# Sheet1.net
KiCad netlist of a schematic drawn in Altium Designer
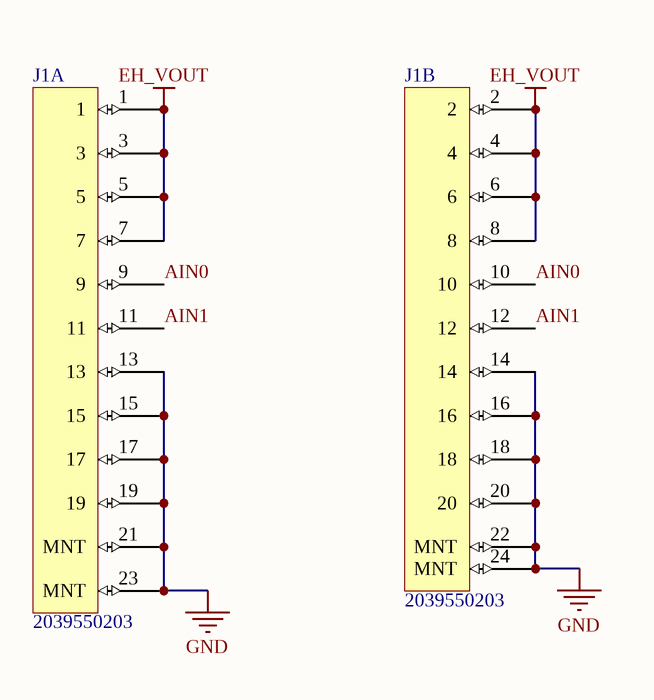
[diagram p0: Sheet1.SchDoc]

(export (version "E")
  (design (tool "Eeschema 10.0.6"))
  (components
    (comp (ref "J1")
      (value "2039550203")
      (footprint "2039550203")
      (libsource (lib "Molex_conn") (part "2039550203"))
    )
  )
  (nets
    (net (code "1") (name "/AIN0") (class "Default")
      (node (ref "J1") (pin "10") (pinfunction "10_10") (pintype "bidirectional"))
      (node (ref "J1") (pin "9") (pinfunction "9_9") (pintype "bidirectional"))
    )
    (net (code "2") (name "/AIN1") (class "Default")
      (node (ref "J1") (pin "11") (pinfunction "11_11") (pintype "bidirectional"))
      (node (ref "J1") (pin "12") (pinfunction "12_12") (pintype "bidirectional"))
    )
    (net (code "3") (name "EH_VOUT") (class "Default")
      (node (ref "J1") (pin "1") (pinfunction "1_1") (pintype "bidirectional"))
      (node (ref "J1") (pin "2") (pinfunction "2_2") (pintype "bidirectional"))
      (node (ref "J1") (pin "3") (pinfunction "3_3") (pintype "bidirectional"))
      (node (ref "J1") (pin "4") (pinfunction "4_4") (pintype "bidirectional"))
      (node (ref "J1") (pin "5") (pinfunction "5_5") (pintype "bidirectional"))
      (node (ref "J1") (pin "6") (pinfunction "6_6") (pintype "bidirectional"))
      (node (ref "J1") (pin "7") (pinfunction "7_7") (pintype "bidirectional"))
      (node (ref "J1") (pin "8") (pinfunction "8_8") (pintype "bidirectional"))
    )
    (net (code "4") (name "GND") (class "Default")
      (node (ref "J1") (pin "13") (pinfunction "13_13") (pintype "bidirectional"))
      (node (ref "J1") (pin "14") (pinfunction "14_14") (pintype "bidirectional"))
      (node (ref "J1") (pin "15") (pinfunction "15_15") (pintype "bidirectional"))
      (node (ref "J1") (pin "16") (pinfunction "16_16") (pintype "bidirectional"))
      (node (ref "J1") (pin "17") (pinfunction "17_17") (pintype "bidirectional"))
      (node (ref "J1") (pin "18") (pinfunction "18_18") (pintype "bidirectional"))
      (node (ref "J1") (pin "19") (pinfunction "19_19") (pintype "bidirectional"))
      (node (ref "J1") (pin "20") (pinfunction "20_20") (pintype "bidirectional"))
      (node (ref "J1") (pin "21") (pinfunction "MNT_21") (pintype "bidirectional"))
      (node (ref "J1") (pin "22") (pinfunction "MNT_22") (pintype "bidirectional"))
      (node (ref "J1") (pin "23") (pinfunction "MNT_23") (pintype "bidirectional"))
      (node (ref "J1") (pin "24") (pinfunction "MNT_24") (pintype "bidirectional"))
    )
  )
)
